# Sheet1.net
KiCad netlist of a schematic drawn in Altium Designer
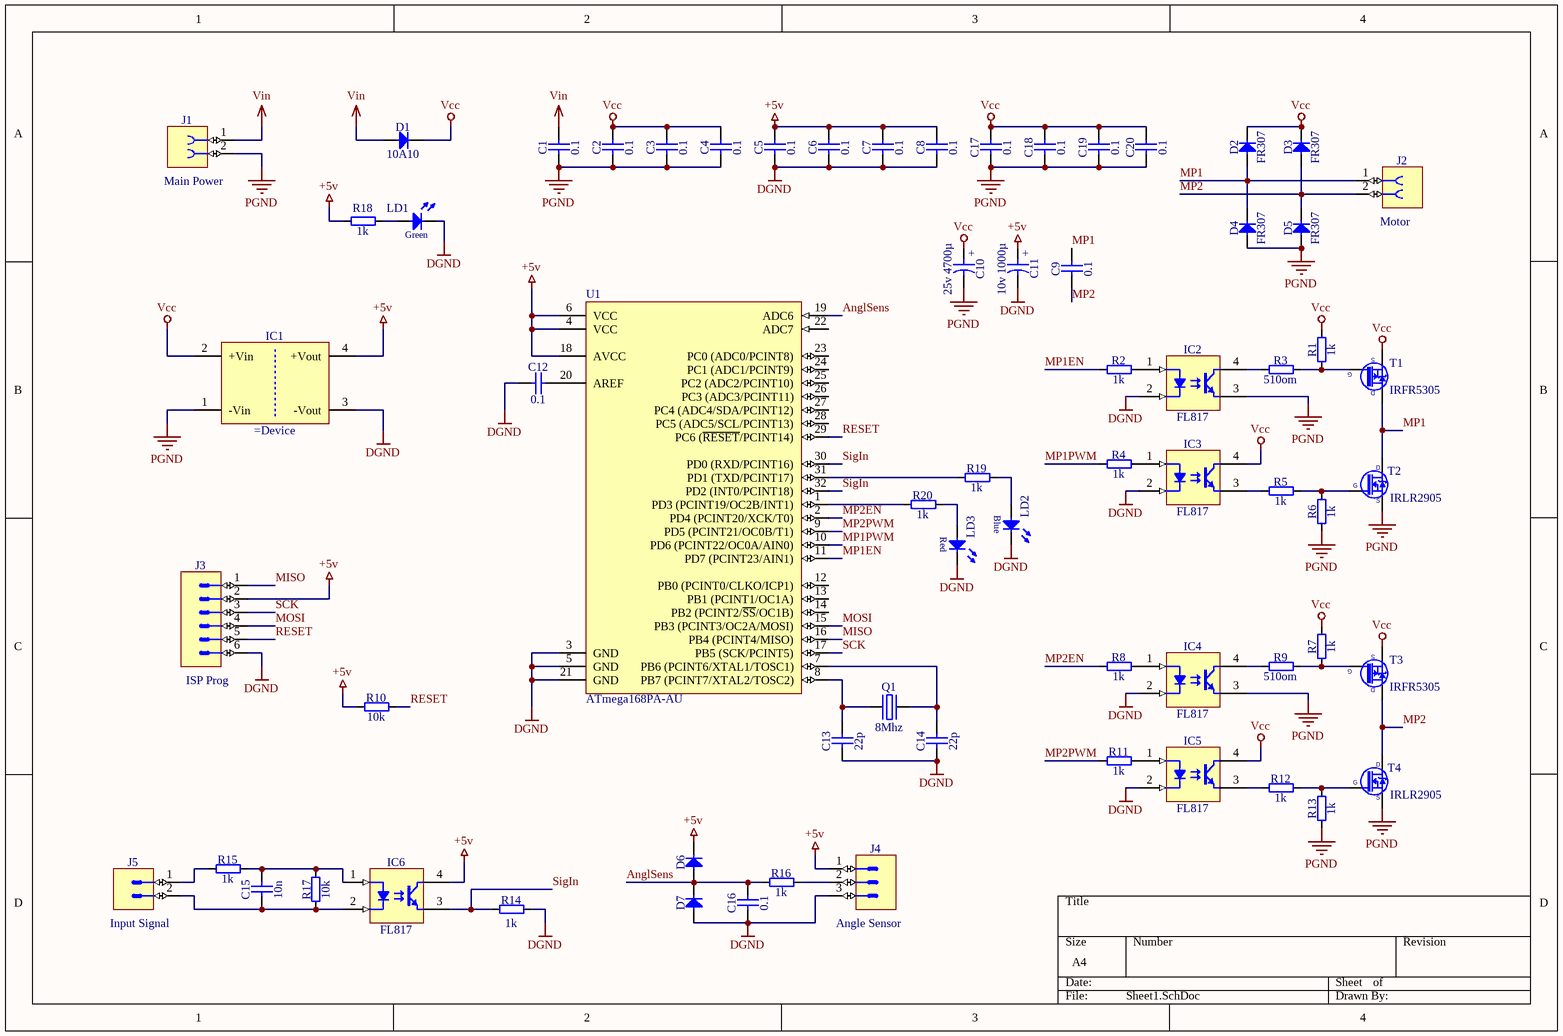
[diagram p0: Sheet1.SchDoc]

(export (version "E")
  (design (tool "Eeschema 10.0.6"))
  (components
    (comp (ref "C1")
      (value "0.1")
      (footprint "Miscellaneous Devices:0402")
      (description "Non-polarised capacitor")
      (libsource (lib "Capacitors") (part "Capacitor - non polarized"))
    )
    (comp (ref "C2")
      (value "0.1")
      (footprint "Miscellaneous Devices:0402")
      (description "Non-polarised capacitor")
      (libsource (lib "Capacitors") (part "Capacitor - non polarized"))
    )
    (comp (ref "C3")
      (value "0.1")
      (footprint "Miscellaneous Devices:0402")
      (description "Non-polarised capacitor")
      (libsource (lib "Capacitors") (part "Capacitor - non polarized"))
    )
    (comp (ref "C4")
      (value "0.1")
      (footprint "Miscellaneous Devices:0402")
      (description "Non-polarised capacitor")
      (libsource (lib "Capacitors") (part "Capacitor - non polarized"))
    )
    (comp (ref "C5")
      (value "0.1")
      (footprint "Miscellaneous Devices:0402")
      (description "Non-polarised capacitor")
      (libsource (lib "Capacitors") (part "Capacitor - non polarized"))
    )
    (comp (ref "C6")
      (value "0.1")
      (footprint "Miscellaneous Devices:0402")
      (description "Non-polarised capacitor")
      (libsource (lib "Capacitors") (part "Capacitor - non polarized"))
    )
    (comp (ref "C7")
      (value "0.1")
      (footprint "Miscellaneous Devices:0402")
      (description "Non-polarised capacitor")
      (libsource (lib "Capacitors") (part "Capacitor - non polarized"))
    )
    (comp (ref "C8")
      (value "0.1")
      (footprint "Miscellaneous Devices:0402")
      (description "Non-polarised capacitor")
      (libsource (lib "Capacitors") (part "Capacitor - non polarized"))
    )
    (comp (ref "C9")
      (value "0.1")
      (footprint "Miscellaneous Devices:0402")
      (description "Non-polarised capacitor")
      (libsource (lib "Capacitors") (part "Capacitor - non polarized"))
    )
    (comp (ref "C10")
      (value "25v 4700µ")
      (footprint "PcbLib1:Cap25v4700mkf")
      (description "Polarised capacitor")
      (libsource (lib "Capacitors") (part "Capacitor - polarized"))
    )
    (comp (ref "C11")
      (value "10v 1000µ")
      (footprint "Capacitors THD:CAPPR350W80D850H1300")
      (description "Polarised capacitor")
      (libsource (lib "Capacitors") (part "Capacitor - polarized"))
    )
    (comp (ref "C12")
      (value "0.1")
      (footprint "Miscellaneous Devices:0402")
      (description "Non-polarised capacitor")
      (libsource (lib "Capacitors") (part "Capacitor - non polarized"))
    )
    (comp (ref "C13")
      (value "22p")
      (footprint "Miscellaneous Devices:0402")
      (description "Non-polarised capacitor")
      (libsource (lib "Capacitors") (part "Capacitor - non polarized"))
    )
    (comp (ref "C14")
      (value "22p")
      (footprint "Miscellaneous Devices:0402")
      (description "Non-polarised capacitor")
      (libsource (lib "Capacitors") (part "Capacitor - non polarized"))
    )
    (comp (ref "C15")
      (value "10n")
      (footprint "Miscellaneous Devices:0402")
      (description "Non-polarised capacitor")
      (libsource (lib "Capacitors") (part "Capacitor - non polarized"))
    )
    (comp (ref "C16")
      (value "0.1")
      (footprint "Miscellaneous Devices:0402")
      (description "Non-polarised capacitor")
      (libsource (lib "Capacitors") (part "Capacitor - non polarized"))
    )
    (comp (ref "C17")
      (value "0.1")
      (footprint "Miscellaneous Devices:0402")
      (description "Non-polarised capacitor")
      (libsource (lib "Capacitors") (part "Capacitor - non polarized"))
    )
    (comp (ref "C18")
      (value "0.1")
      (footprint "Miscellaneous Devices:0402")
      (description "Non-polarised capacitor")
      (libsource (lib "Capacitors") (part "Capacitor - non polarized"))
    )
    (comp (ref "C19")
      (value "0.1")
      (footprint "Miscellaneous Devices:0402")
      (description "Non-polarised capacitor")
      (libsource (lib "Capacitors") (part "Capacitor - non polarized"))
    )
    (comp (ref "C20")
      (value "0.1")
      (footprint "Miscellaneous Devices:0402")
      (description "Non-polarised capacitor")
      (libsource (lib "Capacitors") (part "Capacitor - non polarized"))
    )
    (comp (ref "D1")
      (value "10A10")
      (footprint "PcbLib1:10A10")
      (description "Diode")
      (libsource (lib "Diodes") (part "Diode"))
    )
    (comp (ref "D2")
      (value "FR307")
      (footprint "PcbLib1:DO-27")
      (description "Diode")
      (libsource (lib "Diodes") (part "Diode"))
    )
    (comp (ref "D3")
      (value "FR307")
      (footprint "PcbLib1:DO-27")
      (description "Diode")
      (libsource (lib "Diodes") (part "Diode"))
    )
    (comp (ref "D4")
      (value "FR307")
      (footprint "PcbLib1:DO-27")
      (description "Diode")
      (libsource (lib "Diodes") (part "Diode"))
    )
    (comp (ref "D5")
      (value "FR307")
      (footprint "PcbLib1:DO-27")
      (description "Diode")
      (libsource (lib "Diodes") (part "Diode"))
    )
    (comp (ref "D6")
      (value "~")
      (footprint "ICs And Semiconductors SMD:DIOMELF3515N")
      (description "Diode")
      (libsource (lib "Diodes") (part "Diode"))
    )
    (comp (ref "D7")
      (value "~")
      (footprint "ICs And Semiconductors SMD:DIOMELF3515N")
      (description "Diode")
      (libsource (lib "Diodes") (part "Diode"))
    )
    (comp (ref "IC1")
      (value "~")
      (footprint "ICs And Semiconductors THD:DCDC_TRACO_TME24")
      (description "1kV Isolated 3W Single Output DC-DC Converter")
      (libsource (lib "DC-DC Converters") (part "DCDC_MURATA_MEE3"))
    )
    (comp (ref "IC2")
      (value "FL817")
      (footprint "Miscellaneous Devices:DIP-4")
      (description "Single Optocoupler")
      (libsource (lib "Optocouplers") (part "Optocoupler Type7"))
    )
    (comp (ref "IC3")
      (value "FL817")
      (footprint "Miscellaneous Devices:DIP-4")
      (description "Single Optocoupler")
      (libsource (lib "Optocouplers") (part "Optocoupler Type7"))
    )
    (comp (ref "IC4")
      (value "FL817")
      (footprint "Miscellaneous Devices:DIP-4")
      (description "Single Optocoupler")
      (libsource (lib "Optocouplers") (part "Optocoupler Type7"))
    )
    (comp (ref "IC5")
      (value "FL817")
      (footprint "Miscellaneous Devices:DIP-4")
      (description "Single Optocoupler")
      (libsource (lib "Optocouplers") (part "Optocoupler Type7"))
    )
    (comp (ref "IC6")
      (value "FL817")
      (footprint "Miscellaneous Devices:DIP-4")
      (description "Single Optocoupler")
      (libsource (lib "Optocouplers") (part "Optocoupler Type7"))
    )
    (comp (ref "J1")
      (value "Main Power")
      (footprint "PcbLib1:PwrCon")
      (libsource (lib "Connectors") (part "Connector 2 Female"))
    )
    (comp (ref "J2")
      (value "Motor")
      (footprint "PcbLib1:PwrCon")
      (description "Connector 2 Female")
      (libsource (lib "") (part "Connector 2 Female_1"))
    )
    (comp (ref "J3")
      (value "ISP Prog")
      (footprint "Connectors THD:COMATEL_389.0358.1.06.400")
      (description "Connector 6 Male")
      (libsource (lib "Connectors") (part "Connector 6 Male"))
    )
    (comp (ref "J4")
      (value "Angle Sensor")
      (footprint "Connectors THD:MOLEX_22-05-7038")
      (description "Connector 3 Male")
      (libsource (lib "Connectors") (part "Connector 3 Male"))
    )
    (comp (ref "J5")
      (value "Input Signal")
      (footprint "Connectors THD:MOLEX_22-05-7028")
      (description "Connector 2 Male")
      (libsource (lib "Connectors") (part "Connector 2 Male"))
    )
    (comp (ref "LD1")
      (value "~")
      (footprint "ICs And Semiconductors THD:LED_5MM_GREEN_1C-2A")
      (description "LED Green 1C 2A")
      (libsource (lib "LEDs & Displays") (part "LED Green 1C 2A"))
    )
    (comp (ref "LD2")
      (value "~")
      (footprint "ICs And Semiconductors THD:LED_VISHAY_TSAL6200")
      (description "LED Blue 1C 2A")
      (libsource (lib "LEDs & Displays") (part "LED Blue 1C 2A"))
    )
    (comp (ref "LD3")
      (value "~")
      (footprint "ICs And Semiconductors THD:LED_5MM_RED_1C-2A")
      (description "LED Red 1C 2A")
      (libsource (lib "LEDs & Displays") (part "LED Red 1C 2A"))
    )
    (comp (ref "Q1")
      (value "8Mhz")
      (footprint "ICs And Semiconductors THD:XTAL_HC-49/U")
      (description "Quartz Crystal")
      (libsource (lib "Crystals & Oscillators") (part "Quartz Crystal"))
    )
    (comp (ref "R1")
      (value "1k")
      (footprint "Resistors THD:RES1016-650X250")
      (description "Resistor")
      (libsource (lib "Resistors") (part "Resistor"))
    )
    (comp (ref "R2")
      (value "1k")
      (footprint "Resistors SMD:RESC3116X65N")
      (description "Resistor")
      (libsource (lib "Resistors") (part "Resistor"))
    )
    (comp (ref "R3")
      (value "510om")
      (footprint "Resistors THD:RES1016-650X250")
      (description "Resistor")
      (libsource (lib "Resistors") (part "Resistor"))
    )
    (comp (ref "R4")
      (value "1k")
      (footprint "Resistors SMD:RESC3116X65N")
      (description "Resistor")
      (libsource (lib "Resistors") (part "Resistor"))
    )
    (comp (ref "R5")
      (value "1k")
      (footprint "Resistors THD:RES1016-650X250")
      (description "Resistor")
      (libsource (lib "Resistors") (part "Resistor"))
    )
    (comp (ref "R6")
      (value "1k")
      (footprint "Resistors THD:RES1016-650X250")
      (description "Resistor")
      (libsource (lib "Resistors") (part "Resistor"))
    )
    (comp (ref "R7")
      (value "1k")
      (footprint "Resistors THD:RES1016-650X250")
      (description "Resistor")
      (libsource (lib "Resistors") (part "Resistor"))
    )
    (comp (ref "R8")
      (value "1k")
      (footprint "Resistors SMD:RESC3116X65N")
      (description "Resistor")
      (libsource (lib "Resistors") (part "Resistor"))
    )
    (comp (ref "R9")
      (value "510om")
      (footprint "Resistors THD:RES1016-650X250")
      (description "Resistor")
      (libsource (lib "Resistors") (part "Resistor"))
    )
    (comp (ref "R10")
      (value "10k")
      (footprint "Resistors SMD:RESC3116X65N")
      (description "Resistor")
      (libsource (lib "Resistors") (part "Resistor"))
    )
    (comp (ref "R11")
      (value "1k")
      (footprint "Resistors SMD:RESC3116X65N")
      (description "Resistor")
      (libsource (lib "Resistors") (part "Resistor"))
    )
    (comp (ref "R12")
      (value "1k")
      (footprint "Resistors THD:RES1016-650X250")
      (description "Resistor")
      (libsource (lib "Resistors") (part "Resistor"))
    )
    (comp (ref "R13")
      (value "1k")
      (footprint "Resistors THD:RES1016-650X250")
      (description "Resistor")
      (libsource (lib "Resistors") (part "Resistor"))
    )
    (comp (ref "R14")
      (value "1k")
      (footprint "Resistors SMD:RESC3116X65N")
      (description "Resistor")
      (libsource (lib "Resistors") (part "Resistor"))
    )
    (comp (ref "R15")
      (value "1k")
      (footprint "Resistors SMD:RESC3116X65N")
      (description "Resistor")
      (libsource (lib "Resistors") (part "Resistor"))
    )
    (comp (ref "R16")
      (value "1k")
      (footprint "Resistors SMD:RESC3116X65N")
      (description "Resistor")
      (libsource (lib "Resistors") (part "Resistor"))
    )
    (comp (ref "R17")
      (value "10k")
      (footprint "Resistors SMD:RESC3116X65N")
      (description "Resistor")
      (libsource (lib "Resistors") (part "Resistor"))
    )
    (comp (ref "R18")
      (value "1k")
      (footprint "Resistors SMD:RESC3116X65N")
      (description "Resistor")
      (libsource (lib "Resistors") (part "Resistor"))
    )
    (comp (ref "R19")
      (value "1k")
      (footprint "Resistors SMD:RESC3116X65N")
      (description "Resistor")
      (libsource (lib "Resistors") (part "Resistor"))
    )
    (comp (ref "R20")
      (value "1k")
      (footprint "Resistors SMD:RESC3116X65N")
      (description "Resistor")
      (libsource (lib "Resistors") (part "Resistor"))
    )
    (comp (ref "T1")
      (value "IRFR5305")
      (footprint "ICs And Semiconductors SMD:TO228P991X239-3N-R546X521")
      (description "P-CHANNEL MOSFET WITH ZENER DIODE")
      (libsource (lib "Transistors") (part "P-MOSFET-DZ 1G 2S 3D"))
    )
    (comp (ref "T2")
      (value "IRLR2905")
      (footprint "ICs And Semiconductors SMD:TO228P991X239-3N-R546X521")
      (description "N-CHANNEL MOSFET WITH ZENER DIODE")
      (libsource (lib "Transistors") (part "N-MOSFET-DZ 1G 2S 3D"))
    )
    (comp (ref "T3")
      (value "IRFR5305")
      (footprint "ICs And Semiconductors SMD:TO228P991X239-3N-R546X521")
      (description "P-CHANNEL MOSFET WITH ZENER DIODE")
      (libsource (lib "Transistors") (part "P-MOSFET-DZ 1G 2S 3D"))
    )
    (comp (ref "T4")
      (value "IRLR2905")
      (footprint "ICs And Semiconductors SMD:TO228P991X239-3N-R546X521")
      (description "N-CHANNEL MOSFET WITH ZENER DIODE")
      (libsource (lib "Transistors") (part "N-MOSFET-DZ 1G 2S 3D"))
    )
    (comp (ref "U1")
      (value "ATmega168PA-AU")
      (footprint "32A_M")
      (libsource (lib "Altium Content Vault") (part "CMP-0095-00244-2"))
    )
  )
  (nets
    (net (code "1") (name "+5v") (class "Default")
      (node (ref "C11") (pin "1") (pinfunction "1_1") (pintype "passive"))
      (node (ref "C5") (pin "2") (pinfunction "2_2") (pintype "passive"))
      (node (ref "C6") (pin "2") (pinfunction "2_2") (pintype "passive"))
      (node (ref "C7") (pin "2") (pinfunction "2_2") (pintype "passive"))
      (node (ref "C8") (pin "2") (pinfunction "2_2") (pintype "passive"))
      (node (ref "D6") (pin "1") (pinfunction "C_1") (pintype "passive"))
      (node (ref "IC1") (pin "4") (pinfunction "+Vout_4") (pintype "power_in"))
      (node (ref "IC6") (pin "4") (pinfunction "C_4") (pintype "open_collector"))
      (node (ref "J3") (pin "2") (pinfunction "2_2") (pintype "bidirectional"))
      (node (ref "J4") (pin "1") (pinfunction "1_1") (pintype "bidirectional"))
      (node (ref "R10") (pin "1") (pinfunction "1_1") (pintype "passive"))
      (node (ref "R18") (pin "1") (pinfunction "1_1") (pintype "passive"))
      (node (ref "U1") (pin "18") (pinfunction "AVCC_18") (pintype "power_in"))
      (node (ref "U1") (pin "4") (pinfunction "VCC_4") (pintype "power_in"))
      (node (ref "U1") (pin "6") (pinfunction "VCC_6") (pintype "power_in"))
    )
    (net (code "2") (name "/AnglSens") (class "Default")
      (node (ref "C16") (pin "2") (pinfunction "2_2") (pintype "passive"))
      (node (ref "D6") (pin "2") (pinfunction "A_2") (pintype "passive"))
      (node (ref "D7") (pin "1") (pinfunction "C_1") (pintype "passive"))
      (node (ref "R16") (pin "1") (pinfunction "1_1") (pintype "passive"))
      (node (ref "U1") (pin "19") (pinfunction "ADC6_19") (pintype "input"))
    )
    (net (code "3") (name "/MISO") (class "Default")
      (node (ref "J3") (pin "1") (pinfunction "1_1") (pintype "bidirectional"))
      (node (ref "U1") (pin "16") (pinfunction "PB4_(PCINT4/MISO)_16") (pintype "bidirectional"))
    )
    (net (code "4") (name "/MOSI") (class "Default")
      (node (ref "J3") (pin "4") (pinfunction "4_4") (pintype "bidirectional"))
      (node (ref "U1") (pin "15") (pinfunction "PB3_(PCINT3/OC2A/MOSI)_15") (pintype "bidirectional"))
    )
    (net (code "5") (name "/MP1") (class "Default")
      (node (ref "C9") (pin "2") (pinfunction "2_2") (pintype "passive"))
      (node (ref "D2") (pin "2") (pinfunction "A_2") (pintype "passive"))
      (node (ref "D4") (pin "1") (pinfunction "C_1") (pintype "passive"))
      (node (ref "J2") (pin "1") (pinfunction "1_1") (pintype "bidirectional"))
      (node (ref "T1") (pin "3") (pinfunction "D_3") (pintype "passive"))
      (node (ref "T2") (pin "3") (pinfunction "D_3") (pintype "passive"))
    )
    (net (code "6") (name "/MP1EN") (class "Default")
      (node (ref "R2") (pin "1") (pinfunction "1_1") (pintype "passive"))
      (node (ref "U1") (pin "11") (pinfunction "PD7_(PCINT23/AIN1)_11") (pintype "bidirectional"))
    )
    (net (code "7") (name "/MP1PWM") (class "Default")
      (node (ref "R4") (pin "1") (pinfunction "1_1") (pintype "passive"))
      (node (ref "U1") (pin "10") (pinfunction "PD6_(PCINT22/OC0A/AIN0)_10") (pintype "bidirectional"))
    )
    (net (code "8") (name "/MP2") (class "Default")
      (node (ref "C9") (pin "1") (pinfunction "1_1") (pintype "passive"))
      (node (ref "D3") (pin "2") (pinfunction "A_2") (pintype "passive"))
      (node (ref "D5") (pin "1") (pinfunction "C_1") (pintype "passive"))
      (node (ref "J2") (pin "2") (pinfunction "2_2") (pintype "bidirectional"))
      (node (ref "T3") (pin "3") (pinfunction "D_3") (pintype "passive"))
      (node (ref "T4") (pin "3") (pinfunction "D_3") (pintype "passive"))
    )
    (net (code "9") (name "/MP2EN") (class "Default")
      (node (ref "R8") (pin "1") (pinfunction "1_1") (pintype "passive"))
      (node (ref "U1") (pin "2") (pinfunction "PD4_(PCINT20/XCK/T0)_2") (pintype "bidirectional"))
    )
    (net (code "10") (name "/MP2PWM") (class "Default")
      (node (ref "R11") (pin "1") (pinfunction "1_1") (pintype "passive"))
      (node (ref "U1") (pin "9") (pinfunction "PD5_(PCINT21/OC0B/T1)_9") (pintype "bidirectional"))
    )
    (net (code "11") (name "/RESET") (class "Default")
      (node (ref "J3") (pin "5") (pinfunction "5_5") (pintype "bidirectional"))
      (node (ref "R10") (pin "2") (pinfunction "2_2") (pintype "passive"))
      (node (ref "U1") (pin "29") (pinfunction "PC6_(~{RESET}/PCINT14)_29") (pintype "bidirectional"))
    )
    (net (code "12") (name "/SCK") (class "Default")
      (node (ref "J3") (pin "3") (pinfunction "3_3") (pintype "bidirectional"))
      (node (ref "U1") (pin "17") (pinfunction "PB5_(SCK/PCINT5)_17") (pintype "bidirectional"))
    )
    (net (code "13") (name "/SigIn") (class "Default")
      (node (ref "IC6") (pin "3") (pinfunction "E_3") (pintype "open_emitter"))
      (node (ref "R14") (pin "1") (pinfunction "1_1") (pintype "passive"))
      (node (ref "U1") (pin "30") (pinfunction "PD0_(RXD/PCINT16)_30") (pintype "bidirectional"))
      (node (ref "U1") (pin "32") (pinfunction "PD2_(INT0/PCINT18)_32") (pintype "bidirectional"))
    )
    (net (code "14") (name "DGND") (class "Default")
      (node (ref "C11") (pin "2") (pinfunction "2_2") (pintype "passive"))
      (node (ref "C12") (pin "1") (pinfunction "1_1") (pintype "passive"))
      (node (ref "C13") (pin "1") (pinfunction "1_1") (pintype "passive"))
      (node (ref "C14") (pin "1") (pinfunction "1_1") (pintype "passive"))
      (node (ref "C16") (pin "1") (pinfunction "1_1") (pintype "passive"))
      (node (ref "C5") (pin "1") (pinfunction "1_1") (pintype "passive"))
      (node (ref "C6") (pin "1") (pinfunction "1_1") (pintype "passive"))
      (node (ref "C7") (pin "1") (pinfunction "1_1") (pintype "passive"))
      (node (ref "C8") (pin "1") (pinfunction "1_1") (pintype "passive"))
      (node (ref "D7") (pin "2") (pinfunction "A_2") (pintype "passive"))
      (node (ref "IC1") (pin "3") (pinfunction "-Vout_3") (pintype "power_in"))
      (node (ref "IC2") (pin "2") (pinfunction "C_2") (pintype "input"))
      (node (ref "IC3") (pin "2") (pinfunction "C_2") (pintype "input"))
      (node (ref "IC4") (pin "2") (pinfunction "C_2") (pintype "input"))
      (node (ref "IC5") (pin "2") (pinfunction "C_2") (pintype "input"))
      (node (ref "J3") (pin "6") (pinfunction "6_6") (pintype "bidirectional"))
      (node (ref "J4") (pin "3") (pinfunction "3_3") (pintype "bidirectional"))
      (node (ref "LD1") (pin "1") (pinfunction "C_1") (pintype "passive"))
      (node (ref "LD2") (pin "1") (pinfunction "C_1") (pintype "passive"))
      (node (ref "LD3") (pin "1") (pinfunction "C_1") (pintype "passive"))
      (node (ref "R14") (pin "2") (pinfunction "2_2") (pintype "passive"))
      (node (ref "U1") (pin "21") (pinfunction "GND_21") (pintype "power_in"))
      (node (ref "U1") (pin "3") (pinfunction "GND_3") (pintype "power_in"))
      (node (ref "U1") (pin "5") (pinfunction "GND_5") (pintype "power_in"))
    )
    (net (code "15") (name "Net-(C15-Pad1)") (class "Default")
      (node (ref "C15") (pin "1") (pinfunction "1_1") (pintype "passive"))
      (node (ref "IC6") (pin "2") (pinfunction "C_2") (pintype "input"))
      (node (ref "J5") (pin "2") (pinfunction "2_2") (pintype "bidirectional"))
      (node (ref "R17") (pin "1") (pinfunction "1_1") (pintype "passive"))
    )
    (net (code "16") (name "Net-(IC2-A)") (class "Default")
      (node (ref "IC2") (pin "1") (pinfunction "A_1") (pintype "input"))
      (node (ref "R2") (pin "2") (pinfunction "2_2") (pintype "passive"))
    )
    (net (code "17") (name "Net-(IC2-C-Pad4)") (class "Default")
      (node (ref "IC2") (pin "4") (pinfunction "C_4") (pintype "open_collector"))
      (node (ref "R3") (pin "1") (pinfunction "1_1") (pintype "passive"))
    )
    (net (code "18") (name "Net-(IC3-A)") (class "Default")
      (node (ref "IC3") (pin "1") (pinfunction "A_1") (pintype "input"))
      (node (ref "R4") (pin "2") (pinfunction "2_2") (pintype "passive"))
    )
    (net (code "19") (name "Net-(IC3-E)") (class "Default")
      (node (ref "IC3") (pin "3") (pinfunction "E_3") (pintype "open_emitter"))
      (node (ref "R5") (pin "1") (pinfunction "1_1") (pintype "passive"))
    )
    (net (code "20") (name "Net-(IC4-A)") (class "Default")
      (node (ref "IC4") (pin "1") (pinfunction "A_1") (pintype "input"))
      (node (ref "R8") (pin "2") (pinfunction "2_2") (pintype "passive"))
    )
    (net (code "21") (name "Net-(IC4-C-Pad4)") (class "Default")
      (node (ref "IC4") (pin "4") (pinfunction "C_4") (pintype "open_collector"))
      (node (ref "R9") (pin "1") (pinfunction "1_1") (pintype "passive"))
    )
    (net (code "22") (name "Net-(IC5-A)") (class "Default")
      (node (ref "IC5") (pin "1") (pinfunction "A_1") (pintype "input"))
      (node (ref "R11") (pin "2") (pinfunction "2_2") (pintype "passive"))
    )
    (net (code "23") (name "Net-(IC5-E)") (class "Default")
      (node (ref "IC5") (pin "3") (pinfunction "E_3") (pintype "open_emitter"))
      (node (ref "R12") (pin "1") (pinfunction "1_1") (pintype "passive"))
    )
    (net (code "24") (name "Net-(IC6-A)") (class "Default")
      (node (ref "C15") (pin "2") (pinfunction "2_2") (pintype "passive"))
      (node (ref "IC6") (pin "1") (pinfunction "A_1") (pintype "input"))
      (node (ref "R15") (pin "2") (pinfunction "2_2") (pintype "passive"))
      (node (ref "R17") (pin "2") (pinfunction "2_2") (pintype "passive"))
    )
    (net (code "25") (name "Net-(J4-Pad2)") (class "Default")
      (node (ref "J4") (pin "2") (pinfunction "2_2") (pintype "bidirectional"))
      (node (ref "R16") (pin "2") (pinfunction "2_2") (pintype "passive"))
    )
    (net (code "26") (name "Net-(J5-Pad1)") (class "Default")
      (node (ref "J5") (pin "1") (pinfunction "1_1") (pintype "bidirectional"))
      (node (ref "R15") (pin "1") (pinfunction "1_1") (pintype "passive"))
    )
    (net (code "27") (name "Net-(LD1-A)") (class "Default")
      (node (ref "LD1") (pin "2") (pinfunction "A_2") (pintype "passive"))
      (node (ref "R18") (pin "2") (pinfunction "2_2") (pintype "passive"))
    )
    (net (code "28") (name "Net-(LD2-A)") (class "Default")
      (node (ref "LD2") (pin "2") (pinfunction "A_2") (pintype "passive"))
      (node (ref "R19") (pin "2") (pinfunction "2_2") (pintype "passive"))
    )
    (net (code "29") (name "Net-(LD3-A)") (class "Default")
      (node (ref "LD3") (pin "2") (pinfunction "A_2") (pintype "passive"))
      (node (ref "R20") (pin "2") (pinfunction "2_2") (pintype "passive"))
    )
    (net (code "30") (name "Net-(Q1-OSC1)") (class "Default")
      (node (ref "C13") (pin "2") (pinfunction "2_2") (pintype "passive"))
      (node (ref "Q1") (pin "1") (pinfunction "OSC1_1") (pintype "passive"))
      (node (ref "U1") (pin "8") (pinfunction "PB7_(PCINT7/XTAL2/TOSC2)_8") (pintype "bidirectional"))
    )
    (net (code "31") (name "Net-(Q1-OSC2)") (class "Default")
      (node (ref "C14") (pin "2") (pinfunction "2_2") (pintype "passive"))
      (node (ref "Q1") (pin "2") (pinfunction "OSC2_2") (pintype "passive"))
      (node (ref "U1") (pin "7") (pinfunction "PB6_(PCINT6/XTAL1/TOSC1)_7") (pintype "bidirectional"))
    )
    (net (code "32") (name "Net-(T1-G)") (class "Default")
      (node (ref "R1") (pin "1") (pinfunction "1_1") (pintype "passive"))
      (node (ref "R3") (pin "2") (pinfunction "2_2") (pintype "passive"))
      (node (ref "T1") (pin "1") (pinfunction "G_1") (pintype "passive"))
    )
    (net (code "33") (name "Net-(T2-G)") (class "Default")
      (node (ref "R5") (pin "2") (pinfunction "2_2") (pintype "passive"))
      (node (ref "R6") (pin "2") (pinfunction "2_2") (pintype "passive"))
      (node (ref "T2") (pin "1") (pinfunction "G_1") (pintype "passive"))
    )
    (net (code "34") (name "Net-(T3-G)") (class "Default")
      (node (ref "R7") (pin "1") (pinfunction "1_1") (pintype "passive"))
      (node (ref "R9") (pin "2") (pinfunction "2_2") (pintype "passive"))
      (node (ref "T3") (pin "1") (pinfunction "G_1") (pintype "passive"))
    )
    (net (code "35") (name "Net-(T4-G)") (class "Default")
      (node (ref "R12") (pin "2") (pinfunction "2_2") (pintype "passive"))
      (node (ref "R13") (pin "2") (pinfunction "2_2") (pintype "passive"))
      (node (ref "T4") (pin "1") (pinfunction "G_1") (pintype "passive"))
    )
    (net (code "36") (name "Net-(U1-AREF)") (class "Default")
      (node (ref "C12") (pin "2") (pinfunction "2_2") (pintype "passive"))
      (node (ref "U1") (pin "20") (pinfunction "AREF_20") (pintype "passive"))
    )
    (net (code "37") (name "Net-(U1-PD1_(TXD{slash}PCINT17))") (class "Default")
      (node (ref "R19") (pin "1") (pinfunction "1_1") (pintype "passive"))
      (node (ref "U1") (pin "31") (pinfunction "PD1_(TXD/PCINT17)_31") (pintype "bidirectional"))
    )
    (net (code "38") (name "Net-(U1-PD3_(PCINT19{slash}OC2B{slash}INT1))") (class "Default")
      (node (ref "R20") (pin "1") (pinfunction "1_1") (pintype "passive"))
      (node (ref "U1") (pin "1") (pinfunction "PD3_(PCINT19/OC2B/INT1)_1") (pintype "bidirectional"))
    )
    (net (code "39") (name "PGND") (class "Default")
      (node (ref "C1") (pin "1") (pinfunction "1_1") (pintype "passive"))
      (node (ref "C10") (pin "2") (pinfunction "2_2") (pintype "passive"))
      (node (ref "C17") (pin "1") (pinfunction "1_1") (pintype "passive"))
      (node (ref "C18") (pin "1") (pinfunction "1_1") (pintype "passive"))
      (node (ref "C19") (pin "1") (pinfunction "1_1") (pintype "passive"))
      (node (ref "C2") (pin "1") (pinfunction "1_1") (pintype "passive"))
      (node (ref "C20") (pin "1") (pinfunction "1_1") (pintype "passive"))
      (node (ref "C3") (pin "1") (pinfunction "1_1") (pintype "passive"))
      (node (ref "C4") (pin "1") (pinfunction "1_1") (pintype "passive"))
      (node (ref "D4") (pin "2") (pinfunction "A_2") (pintype "passive"))
      (node (ref "D5") (pin "2") (pinfunction "A_2") (pintype "passive"))
      (node (ref "IC1") (pin "1") (pinfunction "-Vin_1") (pintype "power_in"))
      (node (ref "IC2") (pin "3") (pinfunction "E_3") (pintype "open_emitter"))
      (node (ref "IC4") (pin "3") (pinfunction "E_3") (pintype "open_emitter"))
      (node (ref "J1") (pin "2") (pinfunction "2_2") (pintype "bidirectional"))
      (node (ref "R13") (pin "1") (pinfunction "1_1") (pintype "passive"))
      (node (ref "R6") (pin "1") (pinfunction "1_1") (pintype "passive"))
      (node (ref "T2") (pin "2") (pinfunction "S_2") (pintype "passive"))
      (node (ref "T4") (pin "2") (pinfunction "S_2") (pintype "passive"))
    )
    (net (code "40") (name "Vcc") (class "Default")
      (node (ref "C10") (pin "1") (pinfunction "1_1") (pintype "passive"))
      (node (ref "C17") (pin "2") (pinfunction "2_2") (pintype "passive"))
      (node (ref "C18") (pin "2") (pinfunction "2_2") (pintype "passive"))
      (node (ref "C19") (pin "2") (pinfunction "2_2") (pintype "passive"))
      (node (ref "C2") (pin "2") (pinfunction "2_2") (pintype "passive"))
      (node (ref "C20") (pin "2") (pinfunction "2_2") (pintype "passive"))
      (node (ref "C3") (pin "2") (pinfunction "2_2") (pintype "passive"))
      (node (ref "C4") (pin "2") (pinfunction "2_2") (pintype "passive"))
      (node (ref "D1") (pin "1") (pinfunction "C_1") (pintype "passive"))
      (node (ref "D2") (pin "1") (pinfunction "C_1") (pintype "passive"))
      (node (ref "D3") (pin "1") (pinfunction "C_1") (pintype "passive"))
      (node (ref "IC1") (pin "2") (pinfunction "+Vin_2") (pintype "power_in"))
      (node (ref "IC3") (pin "4") (pinfunction "C_4") (pintype "open_collector"))
      (node (ref "IC5") (pin "4") (pinfunction "C_4") (pintype "open_collector"))
      (node (ref "R1") (pin "2") (pinfunction "2_2") (pintype "passive"))
      (node (ref "R7") (pin "2") (pinfunction "2_2") (pintype "passive"))
      (node (ref "T1") (pin "2") (pinfunction "S_2") (pintype "passive"))
      (node (ref "T3") (pin "2") (pinfunction "S_2") (pintype "passive"))
    )
    (net (code "41") (name "Vin") (class "Default")
      (node (ref "C1") (pin "2") (pinfunction "2_2") (pintype "passive"))
      (node (ref "D1") (pin "2") (pinfunction "A_2") (pintype "passive"))
      (node (ref "J1") (pin "1") (pinfunction "1_1") (pintype "bidirectional"))
    )
    (net (code "42") (name "unconnected-(U1-ADC7-Pad22)") (class "Default")
      (node (ref "U1") (pin "22") (pinfunction "ADC7_22") (pintype "input"))
    )
    (net (code "43") (name "unconnected-(U1-PB0_(PCINT0{slash}CLKO{slash}ICP1)-Pad12)") (class "Default")
      (node (ref "U1") (pin "12") (pinfunction "PB0_(PCINT0/CLKO/ICP1)_12") (pintype "bidirectional"))
    )
    (net (code "44") (name "unconnected-(U1-PB1_(PCINT1{slash}OC1A)-Pad13)") (class "Default")
      (node (ref "U1") (pin "13") (pinfunction "PB1_(PCINT1/OC1A)_13") (pintype "bidirectional"))
    )
    (net (code "45") (name "unconnected-(U1-PB2_(PCINT2{slash}~{SS}{slash}OC1B)-Pad14)") (class "Default")
      (node (ref "U1") (pin "14") (pinfunction "PB2_(PCINT2/~{SS}/OC1B)_14") (pintype "bidirectional"))
    )
    (net (code "46") (name "unconnected-(U1-PC0_(ADC0{slash}PCINT8)-Pad23)") (class "Default")
      (node (ref "U1") (pin "23") (pinfunction "PC0_(ADC0/PCINT8)_23") (pintype "bidirectional"))
    )
    (net (code "47") (name "unconnected-(U1-PC1_(ADC1{slash}PCINT9)-Pad24)") (class "Default")
      (node (ref "U1") (pin "24") (pinfunction "PC1_(ADC1/PCINT9)_24") (pintype "bidirectional"))
    )
    (net (code "48") (name "unconnected-(U1-PC2_(ADC2{slash}PCINT10)-Pad25)") (class "Default")
      (node (ref "U1") (pin "25") (pinfunction "PC2_(ADC2/PCINT10)_25") (pintype "bidirectional"))
    )
    (net (code "49") (name "unconnected-(U1-PC3_(ADC3{slash}PCINT11)-Pad26)") (class "Default")
      (node (ref "U1") (pin "26") (pinfunction "PC3_(ADC3/PCINT11)_26") (pintype "bidirectional"))
    )
    (net (code "50") (name "unconnected-(U1-PC4_(ADC4{slash}SDA{slash}PCINT12)-Pad27)") (class "Default")
      (node (ref "U1") (pin "27") (pinfunction "PC4_(ADC4/SDA/PCINT12)_27") (pintype "bidirectional"))
    )
    (net (code "51") (name "unconnected-(U1-PC5_(ADC5{slash}SCL{slash}PCINT13)-Pad28)") (class "Default")
      (node (ref "U1") (pin "28") (pinfunction "PC5_(ADC5/SCL/PCINT13)_28") (pintype "bidirectional"))
    )
  )
)
